# A131X.net
KiCad netlist of a schematic drawn in EAGLE
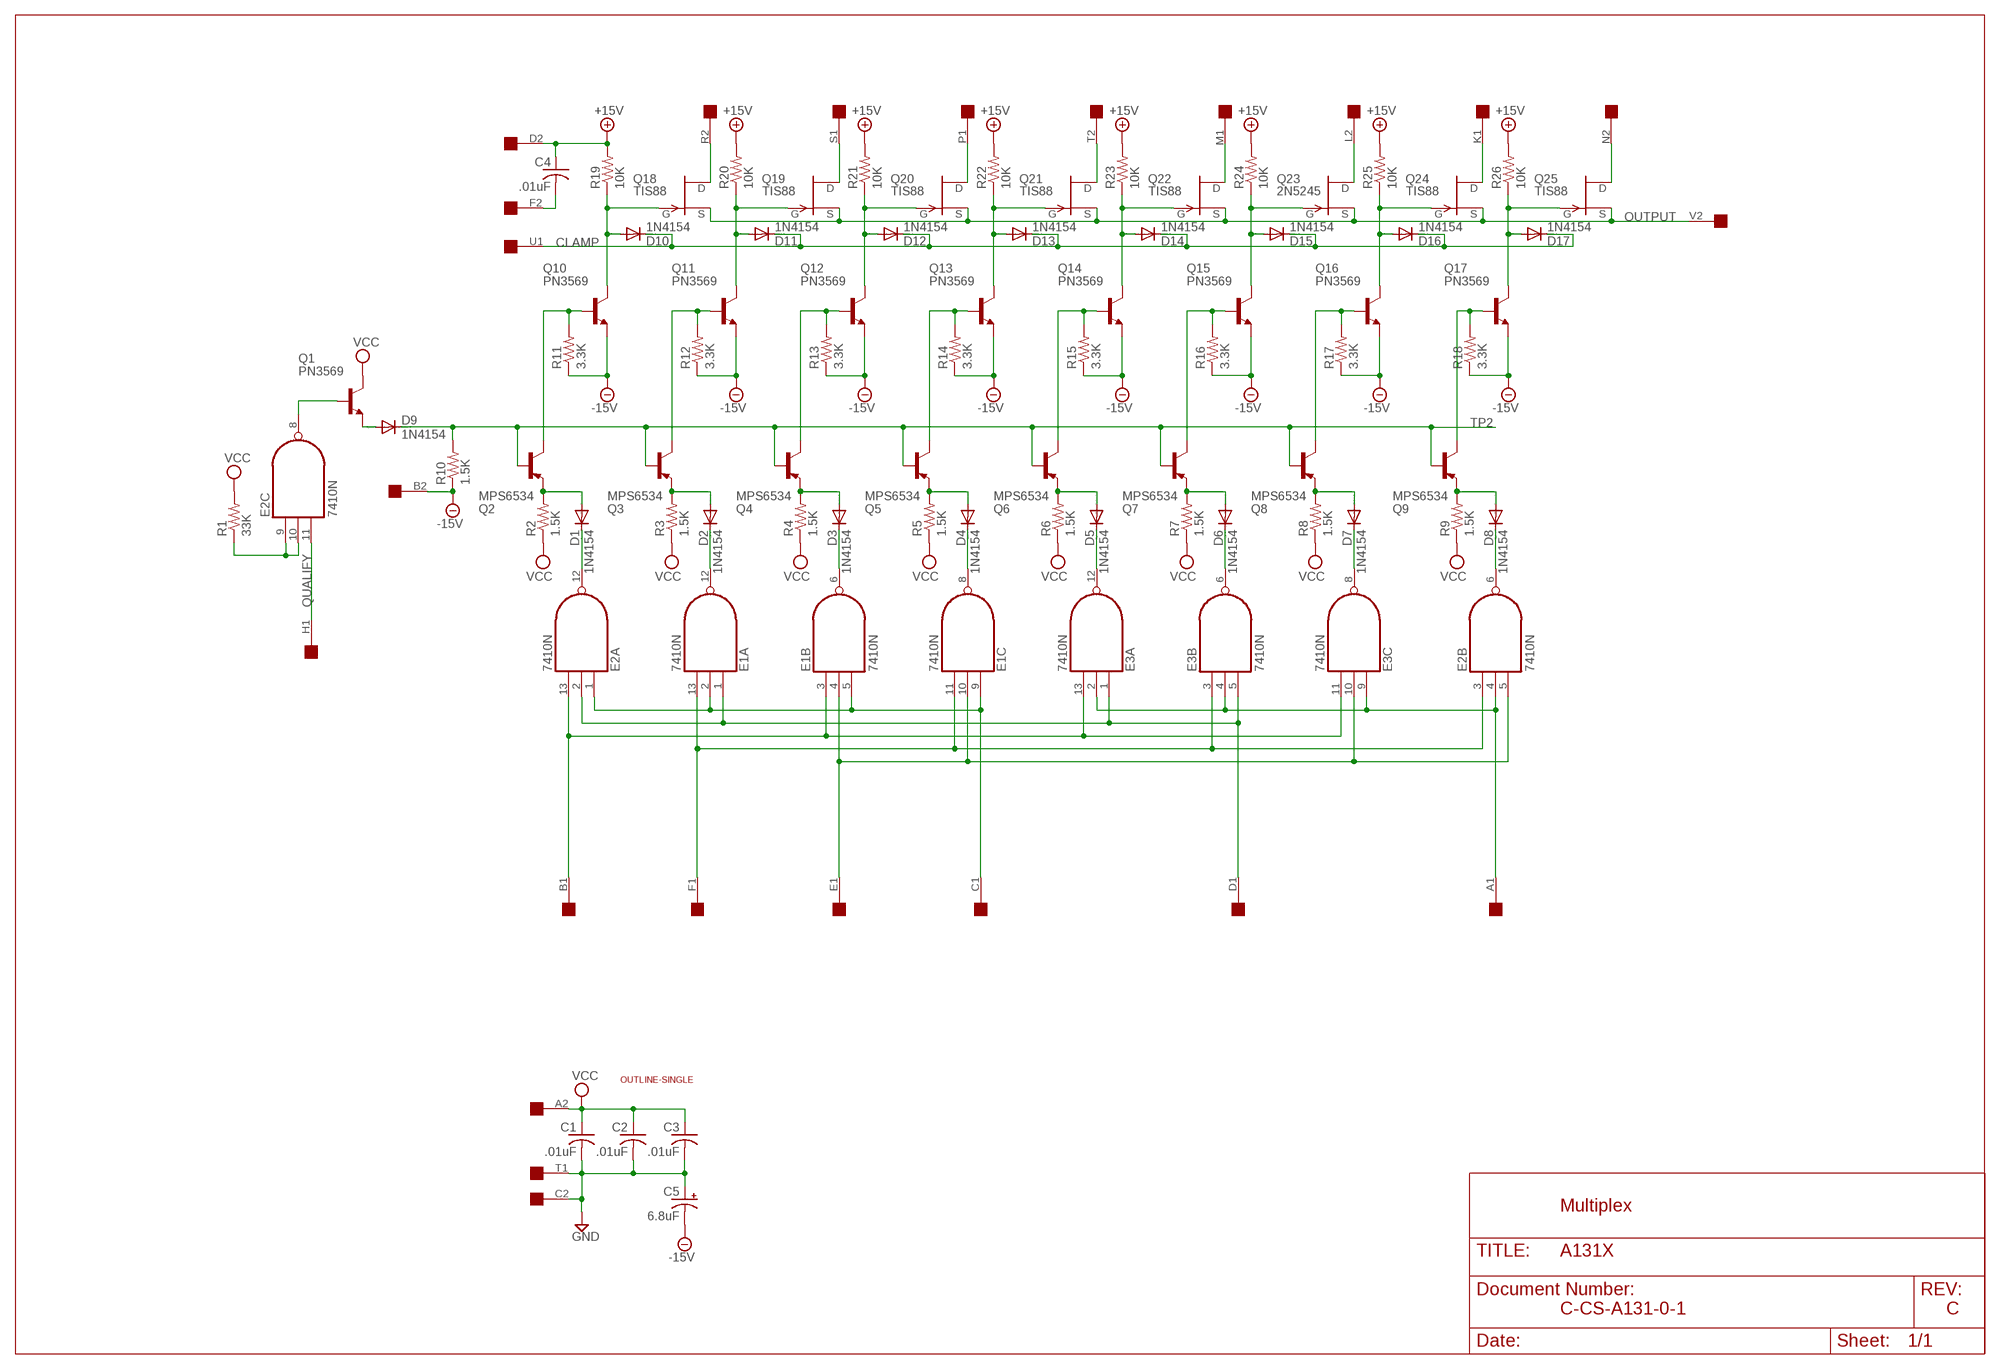
[diagram p0: schematic, sheet 1]

(export (version "E")
  (design (tool "Eeschema 10.0.6"))
  (components
    (comp (ref "C1")
      (value ".01uF")
      (footprint "eagle-import:C050-025X075")
      (libsource (lib "eagle-import") (part "C-US050-025X075"))
    )
    (comp (ref "C2")
      (value ".01uF")
      (footprint "eagle-import:C050-025X075")
      (libsource (lib "eagle-import") (part "C-US050-025X075"))
    )
    (comp (ref "C3")
      (value ".01uF")
      (footprint "eagle-import:C050-025X075")
      (libsource (lib "eagle-import") (part "C-US050-025X075"))
    )
    (comp (ref "C4")
      (value ".01uF")
      (footprint "eagle-import:C050-025X075")
      (libsource (lib "eagle-import") (part "C-US050-025X075"))
    )
    (comp (ref "C5")
      (value "6.8uF")
      (footprint "eagle-import:E12-8")
      (libsource (lib "eagle-import") (part "CPOL-USE20-8AXIAL"))
    )
    (comp (ref "D1")
      (value "1N4154")
      (footprint "eagle-import:DO35-10")
      (libsource (lib "eagle-import") (part "DIODE-DO35-10"))
    )
    (comp (ref "D2")
      (value "1N4154")
      (footprint "eagle-import:DO35-10")
      (libsource (lib "eagle-import") (part "DIODE-DO35-10"))
    )
    (comp (ref "D3")
      (value "1N4154")
      (footprint "eagle-import:DO35-10")
      (libsource (lib "eagle-import") (part "DIODE-DO35-10"))
    )
    (comp (ref "D4")
      (value "1N4154")
      (footprint "eagle-import:DO35-10")
      (libsource (lib "eagle-import") (part "DIODE-DO35-10"))
    )
    (comp (ref "D5")
      (value "1N4154")
      (footprint "eagle-import:DO35-10")
      (libsource (lib "eagle-import") (part "DIODE-DO35-10"))
    )
    (comp (ref "D6")
      (value "1N4154")
      (footprint "eagle-import:DO35-10")
      (libsource (lib "eagle-import") (part "DIODE-DO35-10"))
    )
    (comp (ref "D7")
      (value "1N4154")
      (footprint "eagle-import:DO35-10")
      (libsource (lib "eagle-import") (part "DIODE-DO35-10"))
    )
    (comp (ref "D8")
      (value "1N4154")
      (footprint "eagle-import:DO35-10")
      (libsource (lib "eagle-import") (part "DIODE-DO35-10"))
    )
    (comp (ref "D9")
      (value "1N4154")
      (footprint "eagle-import:DO35-10")
      (libsource (lib "eagle-import") (part "DIODE-DO35-10"))
    )
    (comp (ref "D10")
      (value "1N4154")
      (footprint "eagle-import:DO35-10")
      (libsource (lib "eagle-import") (part "DIODE-DO35-10"))
    )
    (comp (ref "D11")
      (value "1N4154")
      (footprint "eagle-import:DO35-10")
      (libsource (lib "eagle-import") (part "DIODE-DO35-10"))
    )
    (comp (ref "D12")
      (value "1N4154")
      (footprint "eagle-import:DO35-10")
      (libsource (lib "eagle-import") (part "DIODE-DO35-10"))
    )
    (comp (ref "D13")
      (value "1N4154")
      (footprint "eagle-import:DO35-10")
      (libsource (lib "eagle-import") (part "DIODE-DO35-10"))
    )
    (comp (ref "D14")
      (value "1N4154")
      (footprint "eagle-import:DO35-10")
      (libsource (lib "eagle-import") (part "DIODE-DO35-10"))
    )
    (comp (ref "D15")
      (value "1N4154")
      (footprint "eagle-import:DO35-10")
      (libsource (lib "eagle-import") (part "DIODE-DO35-10"))
    )
    (comp (ref "D16")
      (value "1N4154")
      (footprint "eagle-import:DO35-10")
      (libsource (lib "eagle-import") (part "DIODE-DO35-10"))
    )
    (comp (ref "D17")
      (value "1N4154")
      (footprint "eagle-import:DO35-10")
      (libsource (lib "eagle-import") (part "DIODE-DO35-10"))
    )
    (comp (ref "E1")
      (value "7410N")
      (footprint "eagle-import:DIL14")
      (libsource (lib "eagle-import") (part "7410N"))
    )
    (comp (ref "E2")
      (value "7410N")
      (footprint "eagle-import:DIL14")
      (libsource (lib "eagle-import") (part "7410N"))
    )
    (comp (ref "E3")
      (value "7410N")
      (footprint "eagle-import:DIL14")
      (libsource (lib "eagle-import") (part "7410N"))
    )
    (comp (ref "Q1")
      (value "PN3569")
      (footprint "eagle-import:TO5")
      (libsource (lib "eagle-import") (part "-NPN-TO5"))
    )
    (comp (ref "Q2")
      (value "MPS6534")
      (footprint "eagle-import:TO5")
      (libsource (lib "eagle-import") (part "-PNP-TO5"))
    )
    (comp (ref "Q3")
      (value "MPS6534")
      (footprint "eagle-import:TO5")
      (libsource (lib "eagle-import") (part "-PNP-TO5"))
    )
    (comp (ref "Q4")
      (value "MPS6534")
      (footprint "eagle-import:TO5")
      (libsource (lib "eagle-import") (part "-PNP-TO5"))
    )
    (comp (ref "Q5")
      (value "MPS6534")
      (footprint "eagle-import:TO5")
      (libsource (lib "eagle-import") (part "-PNP-TO5"))
    )
    (comp (ref "Q6")
      (value "MPS6534")
      (footprint "eagle-import:TO5")
      (libsource (lib "eagle-import") (part "-PNP-TO5"))
    )
    (comp (ref "Q7")
      (value "MPS6534")
      (footprint "eagle-import:TO5")
      (libsource (lib "eagle-import") (part "-PNP-TO5"))
    )
    (comp (ref "Q8")
      (value "MPS6534")
      (footprint "eagle-import:TO5")
      (libsource (lib "eagle-import") (part "-PNP-TO5"))
    )
    (comp (ref "Q9")
      (value "MPS6534")
      (footprint "eagle-import:TO5")
      (libsource (lib "eagle-import") (part "-PNP-TO5"))
    )
    (comp (ref "Q10")
      (value "PN3569")
      (footprint "eagle-import:TO5")
      (libsource (lib "eagle-import") (part "-NPN-TO5"))
    )
    (comp (ref "Q11")
      (value "PN3569")
      (footprint "eagle-import:TO5")
      (libsource (lib "eagle-import") (part "-NPN-TO5"))
    )
    (comp (ref "Q12")
      (value "PN3569")
      (footprint "eagle-import:TO5")
      (libsource (lib "eagle-import") (part "-NPN-TO5"))
    )
    (comp (ref "Q13")
      (value "PN3569")
      (footprint "eagle-import:TO5")
      (libsource (lib "eagle-import") (part "-NPN-TO5"))
    )
    (comp (ref "Q14")
      (value "PN3569")
      (footprint "eagle-import:TO5")
      (libsource (lib "eagle-import") (part "-NPN-TO5"))
    )
    (comp (ref "Q15")
      (value "PN3569")
      (footprint "eagle-import:TO5")
      (libsource (lib "eagle-import") (part "-NPN-TO5"))
    )
    (comp (ref "Q16")
      (value "PN3569")
      (footprint "eagle-import:TO5")
      (libsource (lib "eagle-import") (part "-NPN-TO5"))
    )
    (comp (ref "Q17")
      (value "PN3569")
      (footprint "eagle-import:TO5")
      (libsource (lib "eagle-import") (part "-NPN-TO5"))
    )
    (comp (ref "Q18")
      (value "TIS88")
      (footprint "eagle-import:TO39")
      (libsource (lib "eagle-import") (part "TIS88"))
    )
    (comp (ref "Q19")
      (value "TIS88")
      (footprint "eagle-import:TO39")
      (libsource (lib "eagle-import") (part "TIS88"))
    )
    (comp (ref "Q20")
      (value "TIS88")
      (footprint "eagle-import:TO39")
      (libsource (lib "eagle-import") (part "TIS88"))
    )
    (comp (ref "Q21")
      (value "TIS88")
      (footprint "eagle-import:TO39")
      (libsource (lib "eagle-import") (part "TIS88"))
    )
    (comp (ref "Q22")
      (value "TIS88")
      (footprint "eagle-import:TO39")
      (libsource (lib "eagle-import") (part "TIS88"))
    )
    (comp (ref "Q23")
      (value "2N5245")
      (footprint "eagle-import:TO39")
      (libsource (lib "eagle-import") (part "TIS88"))
    )
    (comp (ref "Q24")
      (value "TIS88")
      (footprint "eagle-import:TO39")
      (libsource (lib "eagle-import") (part "TIS88"))
    )
    (comp (ref "Q25")
      (value "TIS88")
      (footprint "eagle-import:TO39")
      (libsource (lib "eagle-import") (part "TIS88"))
    )
    (comp (ref "R1")
      (value "33K")
      (footprint "eagle-import:0207_10")
      (libsource (lib "eagle-import") (part "R-US_0207/10"))
    )
    (comp (ref "R2")
      (value "1.5K")
      (footprint "eagle-import:0207_10")
      (libsource (lib "eagle-import") (part "R-US_0207/10"))
    )
    (comp (ref "R3")
      (value "1.5K")
      (footprint "eagle-import:0207_10")
      (libsource (lib "eagle-import") (part "R-US_0207/10"))
    )
    (comp (ref "R4")
      (value "1.5K")
      (footprint "eagle-import:0207_10")
      (libsource (lib "eagle-import") (part "R-US_0207/10"))
    )
    (comp (ref "R5")
      (value "1.5K")
      (footprint "eagle-import:0207_10")
      (libsource (lib "eagle-import") (part "R-US_0207/10"))
    )
    (comp (ref "R6")
      (value "1.5K")
      (footprint "eagle-import:0207_10")
      (libsource (lib "eagle-import") (part "R-US_0207/10"))
    )
    (comp (ref "R7")
      (value "1.5K")
      (footprint "eagle-import:0207_10")
      (libsource (lib "eagle-import") (part "R-US_0207/10"))
    )
    (comp (ref "R8")
      (value "1.5K")
      (footprint "eagle-import:0207_10")
      (libsource (lib "eagle-import") (part "R-US_0207/10"))
    )
    (comp (ref "R9")
      (value "1.5K")
      (footprint "eagle-import:0207_10")
      (libsource (lib "eagle-import") (part "R-US_0207/10"))
    )
    (comp (ref "R10")
      (value "1.5K")
      (footprint "eagle-import:0207_10")
      (libsource (lib "eagle-import") (part "R-US_0207/10"))
    )
    (comp (ref "R11")
      (value "3.3K")
      (footprint "eagle-import:0207_10")
      (libsource (lib "eagle-import") (part "R-US_0207/10"))
    )
    (comp (ref "R12")
      (value "3.3K")
      (footprint "eagle-import:0207_10")
      (libsource (lib "eagle-import") (part "R-US_0207/10"))
    )
    (comp (ref "R13")
      (value "3.3K")
      (footprint "eagle-import:0207_10")
      (libsource (lib "eagle-import") (part "R-US_0207/10"))
    )
    (comp (ref "R14")
      (value "3.3K")
      (footprint "eagle-import:0207_10")
      (libsource (lib "eagle-import") (part "R-US_0207/10"))
    )
    (comp (ref "R15")
      (value "3.3K")
      (footprint "eagle-import:0207_10")
      (libsource (lib "eagle-import") (part "R-US_0207/10"))
    )
    (comp (ref "R16")
      (value "3.3K")
      (footprint "eagle-import:0207_10")
      (libsource (lib "eagle-import") (part "R-US_0207/10"))
    )
    (comp (ref "R17")
      (value "3.3K")
      (footprint "eagle-import:0207_10")
      (libsource (lib "eagle-import") (part "R-US_0207/10"))
    )
    (comp (ref "R18")
      (value "3.3K")
      (footprint "eagle-import:0207_10")
      (libsource (lib "eagle-import") (part "R-US_0207/10"))
    )
    (comp (ref "R19")
      (value "10K")
      (footprint "eagle-import:0207_10")
      (libsource (lib "eagle-import") (part "R-US_0207/10"))
    )
    (comp (ref "R20")
      (value "10K")
      (footprint "eagle-import:0207_10")
      (libsource (lib "eagle-import") (part "R-US_0207/10"))
    )
    (comp (ref "R21")
      (value "10K")
      (footprint "eagle-import:0207_10")
      (libsource (lib "eagle-import") (part "R-US_0207/10"))
    )
    (comp (ref "R22")
      (value "10K")
      (footprint "eagle-import:0207_10")
      (libsource (lib "eagle-import") (part "R-US_0207/10"))
    )
    (comp (ref "R23")
      (value "10K")
      (footprint "eagle-import:0207_10")
      (libsource (lib "eagle-import") (part "R-US_0207/10"))
    )
    (comp (ref "R24")
      (value "10K")
      (footprint "eagle-import:0207_10")
      (libsource (lib "eagle-import") (part "R-US_0207/10"))
    )
    (comp (ref "R25")
      (value "10K")
      (footprint "eagle-import:0207_10")
      (libsource (lib "eagle-import") (part "R-US_0207/10"))
    )
    (comp (ref "R26")
      (value "10K")
      (footprint "eagle-import:0207_10")
      (libsource (lib "eagle-import") (part "R-US_0207/10"))
    )
    (comp (ref "U$1")
      (value "OUTLINE-SINGLE")
      (footprint "eagle-import:SINGLE")
      (libsource (lib "eagle-import") (part "OUTLINE-SINGLE"))
    )
    (comp (ref "U$2")
      (value "SINGLE")
      (footprint "eagle-import:EDGE-CON2")
      (libsource (lib "eagle-import") (part "SINGLE"))
    )
  )
  (nets
    (net (code "1") (name "+15V") (class "Default")
      (node (ref "C4") (pin "1") (pinfunction "1_1") (pintype "passive"))
      (node (ref "R19") (pin "2") (pinfunction "2_2") (pintype "passive"))
      (node (ref "R20") (pin "2") (pinfunction "2_2") (pintype "passive"))
      (node (ref "R21") (pin "2") (pinfunction "2_2") (pintype "passive"))
      (node (ref "R22") (pin "2") (pinfunction "2_2") (pintype "passive"))
      (node (ref "R23") (pin "2") (pinfunction "2_2") (pintype "passive"))
      (node (ref "R24") (pin "2") (pinfunction "2_2") (pintype "passive"))
      (node (ref "R25") (pin "2") (pinfunction "2_2") (pintype "passive"))
      (node (ref "R26") (pin "2") (pinfunction "2_2") (pintype "passive"))
      (node (ref "U$2") (pin "D2") (pinfunction "1_D2") (pintype "bidirectional"))
    )
    (net (code "2") (name "-15V") (class "Default")
      (node (ref "C5") (pin "-") (pinfunction "-_-") (pintype "passive"))
      (node (ref "Q10") (pin "1") (pinfunction "E_1") (pintype "passive"))
      (node (ref "Q11") (pin "1") (pinfunction "E_1") (pintype "passive"))
      (node (ref "Q12") (pin "1") (pinfunction "E_1") (pintype "passive"))
      (node (ref "Q13") (pin "1") (pinfunction "E_1") (pintype "passive"))
      (node (ref "Q14") (pin "1") (pinfunction "E_1") (pintype "passive"))
      (node (ref "Q15") (pin "1") (pinfunction "E_1") (pintype "passive"))
      (node (ref "Q16") (pin "1") (pinfunction "E_1") (pintype "passive"))
      (node (ref "Q17") (pin "1") (pinfunction "E_1") (pintype "passive"))
      (node (ref "R10") (pin "1") (pinfunction "1_1") (pintype "passive"))
      (node (ref "R11") (pin "1") (pinfunction "1_1") (pintype "passive"))
      (node (ref "R12") (pin "1") (pinfunction "1_1") (pintype "passive"))
      (node (ref "R13") (pin "1") (pinfunction "1_1") (pintype "passive"))
      (node (ref "R14") (pin "1") (pinfunction "1_1") (pintype "passive"))
      (node (ref "R15") (pin "1") (pinfunction "1_1") (pintype "passive"))
      (node (ref "R16") (pin "1") (pinfunction "1_1") (pintype "passive"))
      (node (ref "R17") (pin "1") (pinfunction "1_1") (pintype "passive"))
      (node (ref "R18") (pin "1") (pinfunction "1_1") (pintype "passive"))
      (node (ref "U$2") (pin "B2") (pinfunction "1_B2") (pintype "bidirectional"))
    )
    (net (code "3") (name "/CLAMP") (class "Default")
      (node (ref "D10") (pin "C") (pinfunction "C_C") (pintype "passive"))
      (node (ref "D11") (pin "C") (pinfunction "C_C") (pintype "passive"))
      (node (ref "D12") (pin "C") (pinfunction "C_C") (pintype "passive"))
      (node (ref "D13") (pin "C") (pinfunction "C_C") (pintype "passive"))
      (node (ref "D14") (pin "C") (pinfunction "C_C") (pintype "passive"))
      (node (ref "D15") (pin "C") (pinfunction "C_C") (pintype "passive"))
      (node (ref "D16") (pin "C") (pinfunction "C_C") (pintype "passive"))
      (node (ref "D17") (pin "C") (pinfunction "C_C") (pintype "passive"))
      (node (ref "U$2") (pin "U1") (pinfunction "1_U1") (pintype "bidirectional"))
    )
    (net (code "4") (name "/OUTPUT") (class "Default")
      (node (ref "Q18") (pin "1") (pinfunction "S_1") (pintype "passive"))
      (node (ref "Q19") (pin "1") (pinfunction "S_1") (pintype "passive"))
      (node (ref "Q20") (pin "1") (pinfunction "S_1") (pintype "passive"))
      (node (ref "Q21") (pin "1") (pinfunction "S_1") (pintype "passive"))
      (node (ref "Q22") (pin "1") (pinfunction "S_1") (pintype "passive"))
      (node (ref "Q23") (pin "1") (pinfunction "S_1") (pintype "passive"))
      (node (ref "Q24") (pin "1") (pinfunction "S_1") (pintype "passive"))
      (node (ref "Q25") (pin "1") (pinfunction "S_1") (pintype "passive"))
      (node (ref "U$2") (pin "V2") (pinfunction "1_V2") (pintype "bidirectional"))
    )
    (net (code "5") (name "/QUALIFY") (class "Default")
      (node (ref "E2") (pin "11") (pinfunction "I2_11") (pintype "input"))
      (node (ref "U$2") (pin "H1") (pinfunction "1_H1") (pintype "bidirectional"))
    )
    (net (code "6") (name "/TP2") (class "Default")
      (node (ref "D9") (pin "C") (pinfunction "C_C") (pintype "passive"))
      (node (ref "Q2") (pin "2") (pinfunction "B_2") (pintype "passive"))
      (node (ref "Q3") (pin "2") (pinfunction "B_2") (pintype "passive"))
      (node (ref "Q4") (pin "2") (pinfunction "B_2") (pintype "passive"))
      (node (ref "Q5") (pin "2") (pinfunction "B_2") (pintype "passive"))
      (node (ref "Q6") (pin "2") (pinfunction "B_2") (pintype "passive"))
      (node (ref "Q7") (pin "2") (pinfunction "B_2") (pintype "passive"))
      (node (ref "Q8") (pin "2") (pinfunction "B_2") (pintype "passive"))
      (node (ref "Q9") (pin "2") (pinfunction "B_2") (pintype "passive"))
      (node (ref "R10") (pin "2") (pinfunction "2_2") (pintype "passive"))
    )
    (net (code "7") (name "GND") (class "Default")
      (node (ref "C1") (pin "2") (pinfunction "2_2") (pintype "passive"))
      (node (ref "C2") (pin "2") (pinfunction "2_2") (pintype "passive"))
      (node (ref "C3") (pin "2") (pinfunction "2_2") (pintype "passive"))
      (node (ref "C5") (pin "+") (pinfunction "+_+") (pintype "passive"))
      (node (ref "U$2") (pin "C2") (pinfunction "1_C2") (pintype "bidirectional"))
      (node (ref "U$2") (pin "T1") (pinfunction "1_T1") (pintype "bidirectional"))
    )
    (net (code "8") (name "Net-(E1A-I0)") (class "Default")
      (node (ref "E1") (pin "1") (pinfunction "I0_1") (pintype "input"))
      (node (ref "E2") (pin "2") (pinfunction "I1_2") (pintype "input"))
      (node (ref "E3") (pin "1") (pinfunction "I0_1") (pintype "input"))
      (node (ref "E3") (pin "5") (pinfunction "I2_5") (pintype "input"))
      (node (ref "U$2") (pin "D1") (pinfunction "1_D1") (pintype "bidirectional"))
    )
    (net (code "9") (name "Net-(E1A-I1)") (class "Default")
      (node (ref "E1") (pin "2") (pinfunction "I1_2") (pintype "input"))
      (node (ref "E1") (pin "5") (pinfunction "I2_5") (pintype "input"))
      (node (ref "E1") (pin "9") (pinfunction "I0_9") (pintype "input"))
      (node (ref "E2") (pin "1") (pinfunction "I0_1") (pintype "input"))
      (node (ref "U$2") (pin "C1") (pinfunction "1_C1") (pintype "bidirectional"))
    )
    (net (code "10") (name "Net-(E1A-I2)") (class "Default")
      (node (ref "E1") (pin "11") (pinfunction "I2_11") (pintype "input"))
      (node (ref "E1") (pin "13") (pinfunction "I2_13") (pintype "input"))
      (node (ref "E2") (pin "3") (pinfunction "I0_3") (pintype "input"))
      (node (ref "E3") (pin "3") (pinfunction "I0_3") (pintype "input"))
      (node (ref "U$2") (pin "F1") (pinfunction "1_F1") (pintype "bidirectional"))
    )
    (net (code "11") (name "Net-(E1A-O)") (class "Default")
      (node (ref "D2") (pin "C") (pinfunction "C_C") (pintype "passive"))
      (node (ref "E1") (pin "12") (pinfunction "O_12") (pintype "output"))
    )
    (net (code "12") (name "Net-(E1B-I0)") (class "Default")
      (node (ref "E1") (pin "3") (pinfunction "I0_3") (pintype "input"))
      (node (ref "E2") (pin "13") (pinfunction "I2_13") (pintype "input"))
      (node (ref "E3") (pin "11") (pinfunction "I2_11") (pintype "input"))
      (node (ref "E3") (pin "13") (pinfunction "I2_13") (pintype "input"))
      (node (ref "U$2") (pin "B1") (pinfunction "1_B1") (pintype "bidirectional"))
    )
    (net (code "13") (name "Net-(E1B-I1)") (class "Default")
      (node (ref "E1") (pin "10") (pinfunction "I1_10") (pintype "input"))
      (node (ref "E1") (pin "4") (pinfunction "I1_4") (pintype "input"))
      (node (ref "E2") (pin "5") (pinfunction "I2_5") (pintype "input"))
      (node (ref "E3") (pin "10") (pinfunction "I1_10") (pintype "input"))
      (node (ref "U$2") (pin "E1") (pinfunction "1_E1") (pintype "bidirectional"))
    )
    (net (code "14") (name "Net-(E1B-O)") (class "Default")
      (node (ref "D3") (pin "C") (pinfunction "C_C") (pintype "passive"))
      (node (ref "E1") (pin "6") (pinfunction "O_6") (pintype "output"))
    )
    (net (code "15") (name "Net-(E1C-O)") (class "Default")
      (node (ref "D4") (pin "C") (pinfunction "C_C") (pintype "passive"))
      (node (ref "E1") (pin "8") (pinfunction "O_8") (pintype "output"))
    )
    (net (code "16") (name "Net-(E2A-O)") (class "Default")
      (node (ref "D1") (pin "C") (pinfunction "C_C") (pintype "passive"))
      (node (ref "E2") (pin "12") (pinfunction "O_12") (pintype "output"))
    )
    (net (code "17") (name "Net-(E2B-I1)") (class "Default")
      (node (ref "E2") (pin "4") (pinfunction "I1_4") (pintype "input"))
      (node (ref "E3") (pin "2") (pinfunction "I1_2") (pintype "input"))
      (node (ref "E3") (pin "4") (pinfunction "I1_4") (pintype "input"))
      (node (ref "E3") (pin "9") (pinfunction "I0_9") (pintype "input"))
      (node (ref "U$2") (pin "A1") (pinfunction "1_A1") (pintype "bidirectional"))
    )
    (net (code "18") (name "Net-(E2B-O)") (class "Default")
      (node (ref "D8") (pin "C") (pinfunction "C_C") (pintype "passive"))
      (node (ref "E2") (pin "6") (pinfunction "O_6") (pintype "output"))
    )
    (net (code "19") (name "Net-(E2C-I0)") (class "Default")
      (node (ref "E2") (pin "10") (pinfunction "I1_10") (pintype "input"))
      (node (ref "E2") (pin "9") (pinfunction "I0_9") (pintype "input"))
      (node (ref "R1") (pin "1") (pinfunction "1_1") (pintype "passive"))
    )
    (net (code "20") (name "Net-(E2C-O)") (class "Default")
      (node (ref "E2") (pin "8") (pinfunction "O_8") (pintype "output"))
      (node (ref "Q1") (pin "2") (pinfunction "B_2") (pintype "passive"))
    )
    (net (code "21") (name "Net-(E3A-O)") (class "Default")
      (node (ref "D5") (pin "C") (pinfunction "C_C") (pintype "passive"))
      (node (ref "E3") (pin "12") (pinfunction "O_12") (pintype "output"))
    )
    (net (code "22") (name "Net-(E3B-O)") (class "Default")
      (node (ref "D6") (pin "C") (pinfunction "C_C") (pintype "passive"))
      (node (ref "E3") (pin "6") (pinfunction "O_6") (pintype "output"))
    )
    (net (code "23") (name "Net-(E3C-O)") (class "Default")
      (node (ref "D7") (pin "C") (pinfunction "C_C") (pintype "passive"))
      (node (ref "E3") (pin "8") (pinfunction "O_8") (pintype "output"))
    )
    (net (code "24") (name "Net-(Q1-E)") (class "Default")
      (node (ref "D9") (pin "A") (pinfunction "A_A") (pintype "passive"))
      (node (ref "Q1") (pin "1") (pinfunction "E_1") (pintype "passive"))
    )
    (net (code "25") (name "Net-(Q2-E)") (class "Default")
      (node (ref "D1") (pin "A") (pinfunction "A_A") (pintype "passive"))
      (node (ref "Q2") (pin "1") (pinfunction "E_1") (pintype "passive"))
      (node (ref "R2") (pin "2") (pinfunction "2_2") (pintype "passive"))
    )
    (net (code "26") (name "Net-(Q3-E)") (class "Default")
      (node (ref "D2") (pin "A") (pinfunction "A_A") (pintype "passive"))
      (node (ref "Q3") (pin "1") (pinfunction "E_1") (pintype "passive"))
      (node (ref "R3") (pin "2") (pinfunction "2_2") (pintype "passive"))
    )
    (net (code "27") (name "Net-(Q4-E)") (class "Default")
      (node (ref "D3") (pin "A") (pinfunction "A_A") (pintype "passive"))
      (node (ref "Q4") (pin "1") (pinfunction "E_1") (pintype "passive"))
      (node (ref "R4") (pin "2") (pinfunction "2_2") (pintype "passive"))
    )
    (net (code "28") (name "Net-(Q5-E)") (class "Default")
      (node (ref "D4") (pin "A") (pinfunction "A_A") (pintype "passive"))
      (node (ref "Q5") (pin "1") (pinfunction "E_1") (pintype "passive"))
      (node (ref "R5") (pin "2") (pinfunction "2_2") (pintype "passive"))
    )
    (net (code "29") (name "Net-(Q6-E)") (class "Default")
      (node (ref "D5") (pin "A") (pinfunction "A_A") (pintype "passive"))
      (node (ref "Q6") (pin "1") (pinfunction "E_1") (pintype "passive"))
      (node (ref "R6") (pin "2") (pinfunction "2_2") (pintype "passive"))
    )
    (net (code "30") (name "Net-(Q7-E)") (class "Default")
      (node (ref "D6") (pin "A") (pinfunction "A_A") (pintype "passive"))
      (node (ref "Q7") (pin "1") (pinfunction "E_1") (pintype "passive"))
      (node (ref "R7") (pin "2") (pinfunction "2_2") (pintype "passive"))
    )
    (net (code "31") (name "Net-(Q8-E)") (class "Default")
      (node (ref "D7") (pin "A") (pinfunction "A_A") (pintype "passive"))
      (node (ref "Q8") (pin "1") (pinfunction "E_1") (pintype "passive"))
      (node (ref "R8") (pin "2") (pinfunction "2_2") (pintype "passive"))
    )
    (net (code "32") (name "Net-(Q9-E)") (class "Default")
      (node (ref "D8") (pin "A") (pinfunction "A_A") (pintype "passive"))
      (node (ref "Q9") (pin "1") (pinfunction "E_1") (pintype "passive"))
      (node (ref "R9") (pin "2") (pinfunction "2_2") (pintype "passive"))
    )
    (net (code "33") (name "Net-(Q10-B)") (class "Default")
      (node (ref "Q10") (pin "2") (pinfunction "B_2") (pintype "passive"))
      (node (ref "Q2") (pin "3") (pinfunction "C_3") (pintype "passive"))
      (node (ref "R11") (pin "2") (pinfunction "2_2") (pintype "passive"))
    )
    (net (code "34") (name "Net-(Q10-C)") (class "Default")
      (node (ref "D10") (pin "A") (pinfunction "A_A") (pintype "passive"))
      (node (ref "Q10") (pin "3") (pinfunction "C_3") (pintype "passive"))
      (node (ref "Q18") (pin "3") (pinfunction "G_3") (pintype "passive"))
      (node (ref "R19") (pin "1") (pinfunction "1_1") (pintype "passive"))
    )
    (net (code "35") (name "Net-(Q11-B)") (class "Default")
      (node (ref "Q11") (pin "2") (pinfunction "B_2") (pintype "passive"))
      (node (ref "Q3") (pin "3") (pinfunction "C_3") (pintype "passive"))
      (node (ref "R12") (pin "2") (pinfunction "2_2") (pintype "passive"))
    )
    (net (code "36") (name "Net-(Q11-C)") (class "Default")
      (node (ref "D11") (pin "A") (pinfunction "A_A") (pintype "passive"))
      (node (ref "Q11") (pin "3") (pinfunction "C_3") (pintype "passive"))
      (node (ref "Q19") (pin "3") (pinfunction "G_3") (pintype "passive"))
      (node (ref "R20") (pin "1") (pinfunction "1_1") (pintype "passive"))
    )
    (net (code "37") (name "Net-(Q12-B)") (class "Default")
      (node (ref "Q12") (pin "2") (pinfunction "B_2") (pintype "passive"))
      (node (ref "Q4") (pin "3") (pinfunction "C_3") (pintype "passive"))
      (node (ref "R13") (pin "2") (pinfunction "2_2") (pintype "passive"))
    )
    (net (code "38") (name "Net-(Q12-C)") (class "Default")
      (node (ref "D12") (pin "A") (pinfunction "A_A") (pintype "passive"))
      (node (ref "Q12") (pin "3") (pinfunction "C_3") (pintype "passive"))
      (node (ref "Q20") (pin "3") (pinfunction "G_3") (pintype "passive"))
      (node (ref "R21") (pin "1") (pinfunction "1_1") (pintype "passive"))
    )
    (net (code "39") (name "Net-(Q13-B)") (class "Default")
      (node (ref "Q13") (pin "2") (pinfunction "B_2") (pintype "passive"))
      (node (ref "Q5") (pin "3") (pinfunction "C_3") (pintype "passive"))
      (node (ref "R14") (pin "2") (pinfunction "2_2") (pintype "passive"))
    )
    (net (code "40") (name "Net-(Q13-C)") (class "Default")
      (node (ref "D13") (pin "A") (pinfunction "A_A") (pintype "passive"))
      (node (ref "Q13") (pin "3") (pinfunction "C_3") (pintype "passive"))
      (node (ref "Q21") (pin "3") (pinfunction "G_3") (pintype "passive"))
      (node (ref "R22") (pin "1") (pinfunction "1_1") (pintype "passive"))
    )
    (net (code "41") (name "Net-(Q14-B)") (class "Default")
      (node (ref "Q14") (pin "2") (pinfunction "B_2") (pintype "passive"))
      (node (ref "Q6") (pin "3") (pinfunction "C_3") (pintype "passive"))
      (node (ref "R15") (pin "2") (pinfunction "2_2") (pintype "passive"))
    )
    (net (code "42") (name "Net-(Q14-C)") (class "Default")
      (node (ref "D14") (pin "A") (pinfunction "A_A") (pintype "passive"))
      (node (ref "Q14") (pin "3") (pinfunction "C_3") (pintype "passive"))
      (node (ref "Q22") (pin "3") (pinfunction "G_3") (pintype "passive"))
      (node (ref "R23") (pin "1") (pinfunction "1_1") (pintype "passive"))
    )
    (net (code "43") (name "Net-(Q15-B)") (class "Default")
      (node (ref "Q15") (pin "2") (pinfunction "B_2") (pintype "passive"))
      (node (ref "Q7") (pin "3") (pinfunction "C_3") (pintype "passive"))
      (node (ref "R16") (pin "2") (pinfunction "2_2") (pintype "passive"))
    )
    (net (code "44") (name "Net-(Q15-C)") (class "Default")
      (node (ref "D15") (pin "A") (pinfunction "A_A") (pintype "passive"))
      (node (ref "Q15") (pin "3") (pinfunction "C_3") (pintype "passive"))
      (node (ref "Q23") (pin "3") (pinfunction "G_3") (pintype "passive"))
      (node (ref "R24") (pin "1") (pinfunction "1_1") (pintype "passive"))
    )
    (net (code "45") (name "Net-(Q16-B)") (class "Default")
      (node (ref "Q16") (pin "2") (pinfunction "B_2") (pintype "passive"))
      (node (ref "Q8") (pin "3") (pinfunction "C_3") (pintype "passive"))
      (node (ref "R17") (pin "2") (pinfunction "2_2") (pintype "passive"))
    )
    (net (code "46") (name "Net-(Q16-C)") (class "Default")
      (node (ref "D16") (pin "A") (pinfunction "A_A") (pintype "passive"))
      (node (ref "Q16") (pin "3") (pinfunction "C_3") (pintype "passive"))
      (node (ref "Q24") (pin "3") (pinfunction "G_3") (pintype "passive"))
      (node (ref "R25") (pin "1") (pinfunction "1_1") (pintype "passive"))
    )
    (net (code "47") (name "Net-(Q17-B)") (class "Default")
      (node (ref "Q17") (pin "2") (pinfunction "B_2") (pintype "passive"))
      (node (ref "Q9") (pin "3") (pinfunction "C_3") (pintype "passive"))
      (node (ref "R18") (pin "2") (pinfunction "2_2") (pintype "passive"))
    )
    (net (code "48") (name "Net-(Q17-C)") (class "Default")
      (node (ref "D17") (pin "A") (pinfunction "A_A") (pintype "passive"))
      (node (ref "Q17") (pin "3") (pinfunction "C_3") (pintype "passive"))
      (node (ref "Q25") (pin "3") (pinfunction "G_3") (pintype "passive"))
      (node (ref "R26") (pin "1") (pinfunction "1_1") (pintype "passive"))
    )
    (net (code "49") (name "Net-(Q18-D)") (class "Default")
      (node (ref "Q18") (pin "2") (pinfunction "D_2") (pintype "passive"))
      (node (ref "U$2") (pin "R2") (pinfunction "1_R2") (pintype "bidirectional"))
    )
    (net (code "50") (name "Net-(Q19-D)") (class "Default")
      (node (ref "Q19") (pin "2") (pinfunction "D_2") (pintype "passive"))
      (node (ref "U$2") (pin "S1") (pinfunction "1_S1") (pintype "bidirectional"))
    )
    (net (code "51") (name "Net-(Q20-D)") (class "Default")
      (node (ref "Q20") (pin "2") (pinfunction "D_2") (pintype "passive"))
      (node (ref "U$2") (pin "P1") (pinfunction "1_P1") (pintype "bidirectional"))
    )
    (net (code "52") (name "Net-(Q21-D)") (class "Default")
      (node (ref "Q21") (pin "2") (pinfunction "D_2") (pintype "passive"))
      (node (ref "U$2") (pin "T2") (pinfunction "1_T2") (pintype "bidirectional"))
    )
    (net (code "53") (name "Net-(Q22-D)") (class "Default")
      (node (ref "Q22") (pin "2") (pinfunction "D_2") (pintype "passive"))
      (node (ref "U$2") (pin "M1") (pinfunction "1_M1") (pintype "bidirectional"))
    )
    (net (code "54") (name "Net-(Q23-D)") (class "Default")
      (node (ref "Q23") (pin "2") (pinfunction "D_2") (pintype "passive"))
      (node (ref "U$2") (pin "L2") (pinfunction "1_L2") (pintype "bidirectional"))
    )
    (net (code "55") (name "Net-(Q24-D)") (class "Default")
      (node (ref "Q24") (pin "2") (pinfunction "D_2") (pintype "passive"))
      (node (ref "U$2") (pin "K1") (pinfunction "1_K1") (pintype "bidirectional"))
    )
    (net (code "56") (name "Net-(Q25-D)") (class "Default")
      (node (ref "Q25") (pin "2") (pinfunction "D_2") (pintype "passive"))
      (node (ref "U$2") (pin "N2") (pinfunction "1_N2") (pintype "bidirectional"))
    )
    (net (code "57") (name "Net-(U$2L-1)") (class "Default")
      (node (ref "C4") (pin "2") (pinfunction "2_2") (pintype "passive"))
      (node (ref "U$2") (pin "F2") (pinfunction "1_F2") (pintype "bidirectional"))
    )
    (net (code "58") (name "VCC") (class "Default")
      (node (ref "C1") (pin "1") (pinfunction "1_1") (pintype "passive"))
      (node (ref "C2") (pin "1") (pinfunction "1_1") (pintype "passive"))
      (node (ref "C3") (pin "1") (pinfunction "1_1") (pintype "passive"))
      (node (ref "Q1") (pin "3") (pinfunction "C_3") (pintype "passive"))
      (node (ref "R1") (pin "2") (pinfunction "2_2") (pintype "passive"))
      (node (ref "R2") (pin "1") (pinfunction "1_1") (pintype "passive"))
      (node (ref "R3") (pin "1") (pinfunction "1_1") (pintype "passive"))
      (node (ref "R4") (pin "1") (pinfunction "1_1") (pintype "passive"))
      (node (ref "R5") (pin "1") (pinfunction "1_1") (pintype "passive"))
      (node (ref "R6") (pin "1") (pinfunction "1_1") (pintype "passive"))
      (node (ref "R7") (pin "1") (pinfunction "1_1") (pintype "passive"))
      (node (ref "R8") (pin "1") (pinfunction "1_1") (pintype "passive"))
      (node (ref "R9") (pin "1") (pinfunction "1_1") (pintype "passive"))
      (node (ref "U$2") (pin "A2") (pinfunction "1_A2") (pintype "bidirectional"))
    )
  )
)
